# Pg10__NAND_SDMMC_Interface.net
KiCad netlist of a schematic drawn in Altium Designer
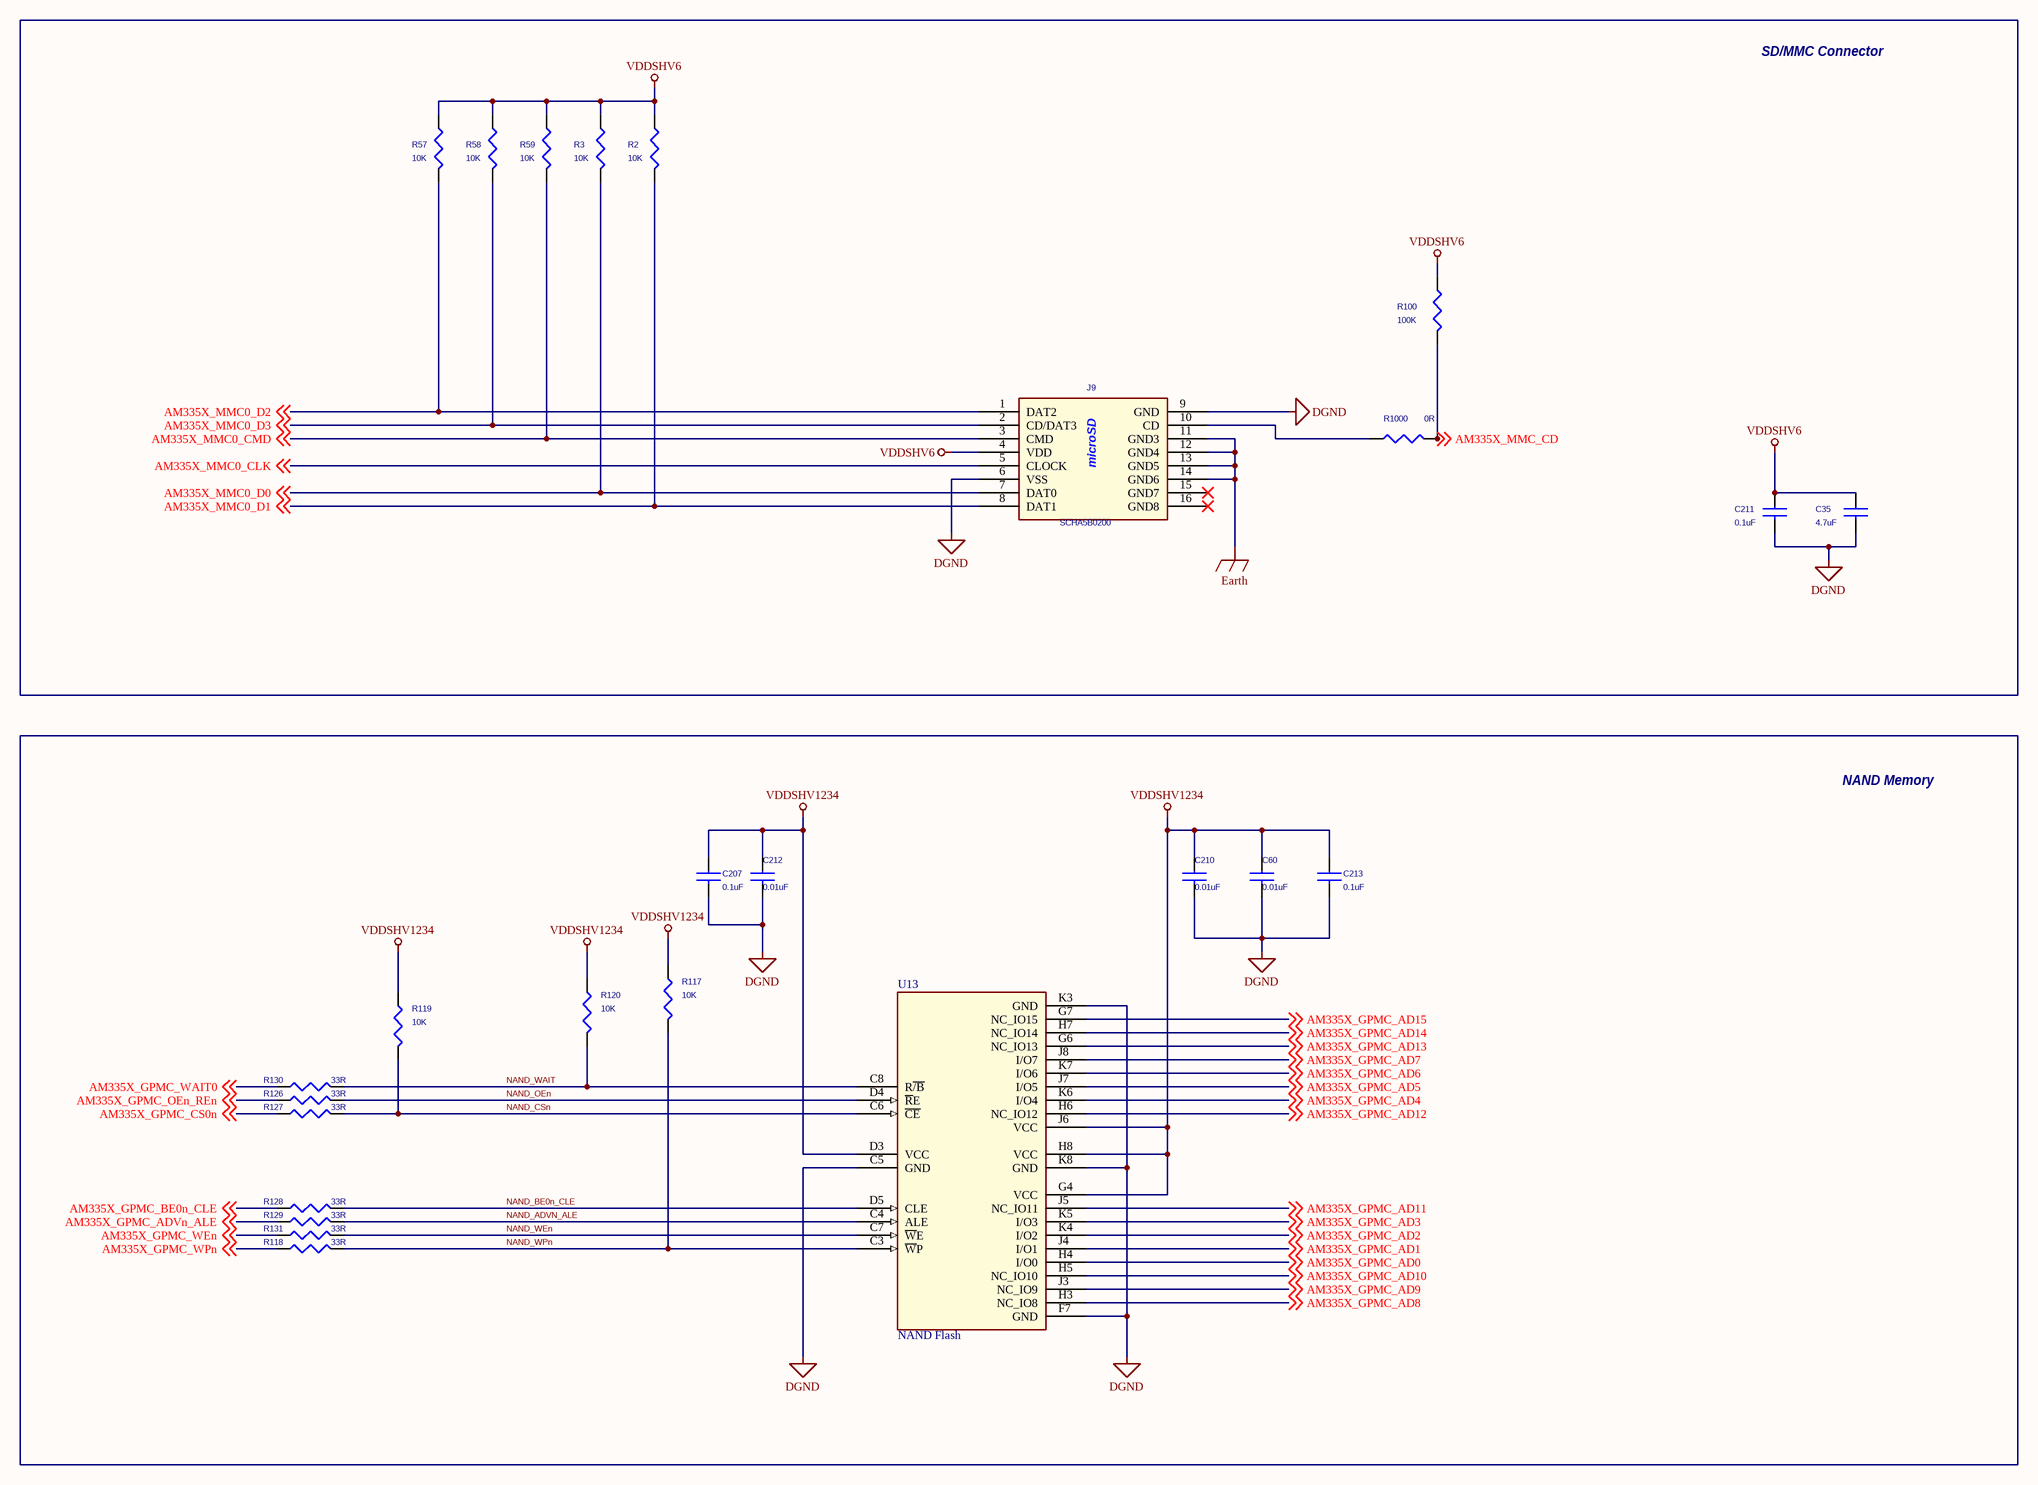
[diagram p0: Pg10_ NAND_SDMMC Interface.SchDoc]

(export (version "E")
  (design (tool "Eeschema 10.0.6"))
  (components
    (comp (ref "C35")
      (value "4.7uF")
      (footprint "SM-7351-CAP-0603")
      (fields (field (name "TIINTPARTNUMBER") "1C0103") (field (name "MFR") "Taiyo Yuden"))
      (libsource (lib "*") (part "4.7uFCapacitor16V10%0603"))
    )
    (comp (ref "C60")
      (value "0.01uF")
      (footprint "SM-7351-CAP-0402")
      (fields (field (name "TIINTPARTNUMBER") "1C0012") (field (name "MFR") "Panasonic"))
      (libsource (lib "*") (part "0.01uFCapacitor16V10%0402"))
    )
    (comp (ref "C207")
      (value "0.1uF")
      (footprint "SM-7351-CAP-0402")
      (fields (field (name "TIINTPARTNUMBER") "1C0089") (field (name "MFR") "Kemet"))
      (libsource (lib "*") (part "0.1uFCapacitor16V10%0402"))
    )
    (comp (ref "C210")
      (value "0.01uF")
      (footprint "SM-7351-CAP-0402")
      (fields (field (name "TIINTPARTNUMBER") "1C0012") (field (name "MFR") "Panasonic"))
      (libsource (lib "*") (part "0.01uFCapacitor16V10%0402"))
    )
    (comp (ref "C211")
      (value "0.1uF")
      (footprint "SM-7351-CAP-0402")
      (fields (field (name "TIINTPARTNUMBER") "1C0089") (field (name "MFR") "Kemet"))
      (libsource (lib "*") (part "0.1uFCapacitor16V10%0402_Dup1"))
    )
    (comp (ref "C212")
      (value "0.01uF")
      (footprint "SM-7351-CAP-0402")
      (fields (field (name "TIINTPARTNUMBER") "1C0012") (field (name "MFR") "Panasonic"))
      (libsource (lib "*") (part "0.01uFCapacitor16V10%0402"))
    )
    (comp (ref "C213")
      (value "0.1uF")
      (footprint "SM-7351-CAP-0402")
      (fields (field (name "TIINTPARTNUMBER") "1C0089") (field (name "MFR") "Kemet"))
      (libsource (lib "*") (part "0.1uFCapacitor16V10%0402"))
    )
    (comp (ref "J9")
      (value "SCHA5B0200")
      (footprint "micro SD")
      (fields (field (name "TIINTPARTNUMBER") "2C0102") (field (name "MFR") "ALPS"))
      (libsource (lib "*") (part "Conn_microSD_8"))
    )
    (comp (ref "R2")
      (value "10K")
      (footprint "SM-7351-RES-0402")
      (description "Resistor 10Kohm 1/16W 5% 0402")
      (fields (field (name "TIINTPARTNUMBER") "1R0168") (field (name "MFR") "Rohm"))
      (libsource (lib "*") (part "10KOhmResistor1/16W0402_Dup1"))
    )
    (comp (ref "R3")
      (value "10K")
      (footprint "SM-7351-RES-0402")
      (description "Resistor 10Kohm 1/16W 5% 0402")
      (fields (field (name "TIINTPARTNUMBER") "1R0168") (field (name "MFR") "Rohm"))
      (libsource (lib "*") (part "10KOhmResistor1/16W0402_Dup1"))
    )
    (comp (ref "R57")
      (value "10K")
      (footprint "SM-7351-RES-0402")
      (description "Resistor 10Kohm 1/16W 5% 0402")
      (fields (field (name "TIINTPARTNUMBER") "1R0168") (field (name "MFR") "Rohm"))
      (libsource (lib "*") (part "10KOhmResistor1/16W0402_Dup1"))
    )
    (comp (ref "R58")
      (value "10K")
      (footprint "SM-7351-RES-0402")
      (description "Resistor 10Kohm 1/16W 5% 0402")
      (fields (field (name "TIINTPARTNUMBER") "1R0168") (field (name "MFR") "Rohm"))
      (libsource (lib "*") (part "10KOhmResistor1/16W0402_Dup1"))
    )
    (comp (ref "R59")
      (value "10K")
      (footprint "SM-7351-RES-0402")
      (description "Resistor 10Kohm 1/16W 5% 0402")
      (fields (field (name "TIINTPARTNUMBER") "1R0168") (field (name "MFR") "Rohm"))
      (libsource (lib "*") (part "10KOhmResistor1/16W0402_Dup1"))
    )
    (comp (ref "R100")
      (value "100K")
      (footprint "SM-7351-RES-0402")
      (description "Resistor 470Kohm 1/16W 1% 0402")
      (fields (field (name "TIINTPARTNUMBER") "1R0190") (field (name "MFR") "Stackpole Electronics"))
      (libsource (lib "*") (part "470Kohm1/16W1%SMD0402"))
    )
    (comp (ref "R117")
      (value "10K")
      (footprint "SM-7351-RES-0402")
      (fields (field (name "TIINTPARTNUMBER") "1R0168") (field (name "MFR") "Rohm"))
      (libsource (lib "*") (part "10KOhmResistor1/16W0402"))
    )
    (comp (ref "R118")
      (value "33R")
      (footprint "SM-7351-RES-0402")
      (fields (field (name "TIINTPARTNUMBER") "1R0168") (field (name "MFR") "Rohm"))
      (libsource (lib "*") (part "10KOhmResistor1/16W0402"))
    )
    (comp (ref "R119")
      (value "10K")
      (footprint "SM-7351-RES-0402")
      (fields (field (name "TIINTPARTNUMBER") "1R0168") (field (name "MFR") "Rohm"))
      (libsource (lib "*") (part "10KOhmResistor1/16W0402"))
    )
    (comp (ref "R120")
      (value "10K")
      (footprint "SM-7351-RES-0402")
      (fields (field (name "TIINTPARTNUMBER") "1R0168") (field (name "MFR") "Rohm"))
      (libsource (lib "*") (part "10KOhmResistor1/16W0402"))
    )
    (comp (ref "R126")
      (value "33R")
      (footprint "SM-7351-RES-0402")
      (fields (field (name "TIINTPARTNUMBER") "1R0168") (field (name "MFR") "Rohm"))
      (libsource (lib "*") (part "10KOhmResistor1/16W0402"))
    )
    (comp (ref "R127")
      (value "33R")
      (footprint "SM-7351-RES-0402")
      (fields (field (name "TIINTPARTNUMBER") "1R0168") (field (name "MFR") "Rohm"))
      (libsource (lib "*") (part "10KOhmResistor1/16W0402"))
    )
    (comp (ref "R128")
      (value "33R")
      (footprint "SM-7351-RES-0402")
      (fields (field (name "TIINTPARTNUMBER") "1R0168") (field (name "MFR") "Rohm"))
      (libsource (lib "*") (part "10KOhmResistor1/16W0402"))
    )
    (comp (ref "R129")
      (value "33R")
      (footprint "SM-7351-RES-0402")
      (fields (field (name "TIINTPARTNUMBER") "1R0168") (field (name "MFR") "Rohm"))
      (libsource (lib "*") (part "10KOhmResistor1/16W0402"))
    )
    (comp (ref "R130")
      (value "33R")
      (footprint "SM-7351-RES-0402")
      (fields (field (name "TIINTPARTNUMBER") "1R0168") (field (name "MFR") "Rohm"))
      (libsource (lib "*") (part "10KOhmResistor1/16W0402"))
    )
    (comp (ref "R131")
      (value "33R")
      (footprint "SM-7351-RES-0402")
      (fields (field (name "TIINTPARTNUMBER") "1R0168") (field (name "MFR") "Rohm"))
      (libsource (lib "*") (part "10KOhmResistor1/16W0402"))
    )
    (comp (ref "R1000")
      (value "0R")
      (footprint "SM-7351-RES-0402")
      (description "Resistor 470Kohm 1/16W 1% 0402")
      (fields (field (name "TIINTPARTNUMBER") "1R0190") (field (name "MFR") "Stackpole Electronics"))
      (libsource (lib "*") (part "470Kohm1/16W1%SMD0402"))
    )
    (comp (ref "U13")
      (value "NAND Flash")
      (footprint "VFBGA - 63")
      (description "MT29F2Gxx")
      (fields (field (name "PARTNUMBER") "557-1486-2-ND"))
      (libsource (lib "ARMflash_mini") (part "NAND Flash"))
    )
  )
  (nets
    (net (code "1") (name "/NAND_ADVN_ALE") (class "Default")
      (node (ref "R129") (pin "1") (pinfunction "P1_1") (pintype "passive"))
      (node (ref "U13") (pin "C4") (pinfunction "ALE_C4") (pintype "input"))
    )
    (net (code "2") (name "/NAND_BE0n_CLE") (class "Default")
      (node (ref "R128") (pin "1") (pinfunction "P1_1") (pintype "passive"))
      (node (ref "U13") (pin "D5") (pinfunction "CLE_D5") (pintype "input"))
    )
    (net (code "3") (name "/NAND_CSn") (class "Default")
      (node (ref "R119") (pin "1") (pinfunction "P1_1") (pintype "passive"))
      (node (ref "R127") (pin "1") (pinfunction "P1_1") (pintype "passive"))
      (node (ref "U13") (pin "C6") (pinfunction "~{CE}_C6") (pintype "input"))
    )
    (net (code "4") (name "/NAND_OEn") (class "Default")
      (node (ref "R126") (pin "1") (pinfunction "P1_1") (pintype "passive"))
      (node (ref "U13") (pin "D4") (pinfunction "~{R}E_D4") (pintype "input"))
    )
    (net (code "5") (name "/NAND_WAIT") (class "Default")
      (node (ref "R120") (pin "1") (pinfunction "P1_1") (pintype "passive"))
      (node (ref "R130") (pin "1") (pinfunction "P1_1") (pintype "passive"))
      (node (ref "U13") (pin "C8") (pinfunction "R~{/B}_C8") (pintype "open_collector"))
    )
    (net (code "6") (name "/NAND_WEn") (class "Default")
      (node (ref "R131") (pin "1") (pinfunction "P1_1") (pintype "passive"))
      (node (ref "U13") (pin "C7") (pinfunction "~{W}E_C7") (pintype "input"))
    )
    (net (code "7") (name "/NAND_WPn") (class "Default")
      (node (ref "R117") (pin "1") (pinfunction "P1_1") (pintype "passive"))
      (node (ref "R118") (pin "1") (pinfunction "P1_1") (pintype "passive"))
      (node (ref "U13") (pin "C3") (pinfunction "~{W}P_C3") (pintype "input"))
    )
    (net (code "8") (name "AM335X_GPMC_AD0") (class "Default")
      (node (ref "U13") (pin "H4") (pinfunction "I/O0_H4") (pintype "tri_state"))
    )
    (net (code "9") (name "AM335X_GPMC_AD1") (class "Default")
      (node (ref "U13") (pin "J4") (pinfunction "I/O1_J4") (pintype "tri_state"))
    )
    (net (code "10") (name "AM335X_GPMC_AD2") (class "Default")
      (node (ref "U13") (pin "K4") (pinfunction "I/O2_K4") (pintype "tri_state"))
    )
    (net (code "11") (name "AM335X_GPMC_AD3") (class "Default")
      (node (ref "U13") (pin "K5") (pinfunction "I/O3_K5") (pintype "tri_state"))
    )
    (net (code "12") (name "AM335X_GPMC_AD4") (class "Default")
      (node (ref "U13") (pin "K6") (pinfunction "I/O4_K6") (pintype "tri_state"))
    )
    (net (code "13") (name "AM335X_GPMC_AD5") (class "Default")
      (node (ref "U13") (pin "J7") (pinfunction "I/O5_J7") (pintype "tri_state"))
    )
    (net (code "14") (name "AM335X_GPMC_AD6") (class "Default")
      (node (ref "U13") (pin "K7") (pinfunction "I/O6_K7") (pintype "tri_state"))
    )
    (net (code "15") (name "AM335X_GPMC_AD7") (class "Default")
      (node (ref "U13") (pin "J8") (pinfunction "I/O7_J8") (pintype "tri_state"))
    )
    (net (code "16") (name "AM335X_GPMC_AD8") (class "Default")
      (node (ref "U13") (pin "H3") (pinfunction "NC_IO8_H3") (pintype "passive"))
    )
    (net (code "17") (name "AM335X_GPMC_AD9") (class "Default")
      (node (ref "U13") (pin "J3") (pinfunction "NC_IO9_J3") (pintype "passive"))
    )
    (net (code "18") (name "AM335X_GPMC_AD10") (class "Default")
      (node (ref "U13") (pin "H5") (pinfunction "NC_IO10_H5") (pintype "passive"))
    )
    (net (code "19") (name "AM335X_GPMC_AD11") (class "Default")
      (node (ref "U13") (pin "J5") (pinfunction "NC_IO11_J5") (pintype "passive"))
    )
    (net (code "20") (name "AM335X_GPMC_AD12") (class "Default")
      (node (ref "U13") (pin "H6") (pinfunction "NC_IO12_H6") (pintype "passive"))
    )
    (net (code "21") (name "AM335X_GPMC_AD13") (class "Default")
      (node (ref "U13") (pin "G6") (pinfunction "NC_IO13_G6") (pintype "passive"))
    )
    (net (code "22") (name "AM335X_GPMC_AD14") (class "Default")
      (node (ref "U13") (pin "H7") (pinfunction "NC_IO14_H7") (pintype "passive"))
    )
    (net (code "23") (name "AM335X_GPMC_AD15") (class "Default")
      (node (ref "U13") (pin "G7") (pinfunction "NC_IO15_G7") (pintype "passive"))
    )
    (net (code "24") (name "AM335X_GPMC_ADVn_ALE") (class "Default")
      (node (ref "R129") (pin "2") (pinfunction "P2_2") (pintype "passive"))
    )
    (net (code "25") (name "AM335X_GPMC_BE0n_CLE") (class "Default")
      (node (ref "R128") (pin "2") (pinfunction "P2_2") (pintype "passive"))
    )
    (net (code "26") (name "AM335X_GPMC_CS0n") (class "Default")
      (node (ref "R127") (pin "2") (pinfunction "P2_2") (pintype "passive"))
    )
    (net (code "27") (name "AM335X_GPMC_OEn_REn") (class "Default")
      (node (ref "R126") (pin "2") (pinfunction "P2_2") (pintype "passive"))
    )
    (net (code "28") (name "AM335X_GPMC_WAIT0") (class "Default")
      (node (ref "R130") (pin "2") (pinfunction "P2_2") (pintype "passive"))
    )
    (net (code "29") (name "AM335X_GPMC_WEn") (class "Default")
      (node (ref "R131") (pin "2") (pinfunction "P2_2") (pintype "passive"))
    )
    (net (code "30") (name "AM335X_GPMC_WPn") (class "Default")
      (node (ref "R118") (pin "2") (pinfunction "P2_2") (pintype "passive"))
    )
    (net (code "31") (name "AM335X_MMC0_CLK") (class "Default")
      (node (ref "J9") (pin "5") (pinfunction "CLOCK_5") (pintype "passive"))
    )
    (net (code "32") (name "AM335X_MMC0_CMD") (class "Default")
      (node (ref "J9") (pin "3") (pinfunction "CMD_3") (pintype "passive"))
      (node (ref "R59") (pin "1") (pinfunction "P1_1") (pintype "passive"))
    )
    (net (code "33") (name "AM335X_MMC0_D0") (class "Default")
      (node (ref "J9") (pin "7") (pinfunction "DAT0_7") (pintype "passive"))
      (node (ref "R3") (pin "1") (pinfunction "P1_1") (pintype "passive"))
    )
    (net (code "34") (name "AM335X_MMC0_D1") (class "Default")
      (node (ref "J9") (pin "8") (pinfunction "DAT1_8") (pintype "passive"))
      (node (ref "R2") (pin "1") (pinfunction "P1_1") (pintype "passive"))
    )
    (net (code "35") (name "AM335X_MMC0_D2") (class "Default")
      (node (ref "J9") (pin "1") (pinfunction "DAT2_1") (pintype "passive"))
      (node (ref "R57") (pin "1") (pinfunction "P1_1") (pintype "passive"))
    )
    (net (code "36") (name "AM335X_MMC0_D3") (class "Default")
      (node (ref "J9") (pin "2") (pinfunction "CD/DAT3_2") (pintype "passive"))
      (node (ref "R58") (pin "1") (pinfunction "P1_1") (pintype "passive"))
    )
    (net (code "37") (name "AM335X_MMC_CD") (class "Default")
      (node (ref "R100") (pin "1") (pinfunction "P1_1") (pintype "passive"))
      (node (ref "R1000") (pin "1") (pinfunction "P1_1") (pintype "passive"))
    )
    (net (code "38") (name "DGND") (class "Default")
      (node (ref "C207") (pin "2") (pinfunction "2_2") (pintype "passive"))
      (node (ref "C210") (pin "2") (pinfunction "2_2") (pintype "passive"))
      (node (ref "C211") (pin "2") (pinfunction "2_2") (pintype "passive"))
      (node (ref "C212") (pin "2") (pinfunction "2_2") (pintype "passive"))
      (node (ref "C213") (pin "2") (pinfunction "2_2") (pintype "passive"))
      (node (ref "C35") (pin "2") (pinfunction "2_2") (pintype "passive"))
      (node (ref "C60") (pin "2") (pinfunction "2_2") (pintype "passive"))
      (node (ref "J9") (pin "6") (pinfunction "VSS_6") (pintype "power_in"))
      (node (ref "J9") (pin "9") (pinfunction "GND_9") (pintype "power_in"))
      (node (ref "U13") (pin "C5") (pinfunction "GND_C5") (pintype "power_in"))
      (node (ref "U13") (pin "F7") (pinfunction "GND_F7") (pintype "power_in"))
      (node (ref "U13") (pin "K3") (pinfunction "GND_K3") (pintype "power_in"))
      (node (ref "U13") (pin "K8") (pinfunction "GND_K8") (pintype "power_in"))
    )
    (net (code "39") (name "Earth") (class "Default")
      (node (ref "J9") (pin "11") (pinfunction "GND3_11") (pintype "power_in"))
      (node (ref "J9") (pin "12") (pinfunction "GND4_12") (pintype "power_in"))
      (node (ref "J9") (pin "13") (pinfunction "GND5_13") (pintype "power_in"))
      (node (ref "J9") (pin "14") (pinfunction "GND6_14") (pintype "power_in"))
    )
    (net (code "40") (name "Net-(J9-CD)") (class "Default")
      (node (ref "J9") (pin "10") (pinfunction "CD_10") (pintype "passive"))
      (node (ref "R1000") (pin "2") (pinfunction "P2_2") (pintype "passive"))
    )
    (net (code "41") (name "VDDSHV6") (class "Default")
      (node (ref "C211") (pin "1") (pinfunction "1_1") (pintype "passive"))
      (node (ref "C35") (pin "1") (pinfunction "1_1") (pintype "passive"))
      (node (ref "J9") (pin "4") (pinfunction "VDD_4") (pintype "power_in"))
      (node (ref "R100") (pin "2") (pinfunction "P2_2") (pintype "passive"))
      (node (ref "R2") (pin "2") (pinfunction "P2_2") (pintype "passive"))
      (node (ref "R3") (pin "2") (pinfunction "P2_2") (pintype "passive"))
      (node (ref "R57") (pin "2") (pinfunction "P2_2") (pintype "passive"))
      (node (ref "R58") (pin "2") (pinfunction "P2_2") (pintype "passive"))
      (node (ref "R59") (pin "2") (pinfunction "P2_2") (pintype "passive"))
    )
    (net (code "42") (name "VDDSHV1234") (class "Default")
      (node (ref "C207") (pin "1") (pinfunction "1_1") (pintype "passive"))
      (node (ref "C210") (pin "1") (pinfunction "1_1") (pintype "passive"))
      (node (ref "C212") (pin "1") (pinfunction "1_1") (pintype "passive"))
      (node (ref "C213") (pin "1") (pinfunction "1_1") (pintype "passive"))
      (node (ref "C60") (pin "1") (pinfunction "1_1") (pintype "passive"))
      (node (ref "R117") (pin "2") (pinfunction "P2_2") (pintype "passive"))
      (node (ref "R119") (pin "2") (pinfunction "P2_2") (pintype "passive"))
      (node (ref "R120") (pin "2") (pinfunction "P2_2") (pintype "passive"))
      (node (ref "U13") (pin "D3") (pinfunction "VCC_D3") (pintype "power_in"))
      (node (ref "U13") (pin "G4") (pinfunction "VCC_G4") (pintype "power_in"))
      (node (ref "U13") (pin "H8") (pinfunction "VCC_H8") (pintype "power_in"))
      (node (ref "U13") (pin "J6") (pinfunction "VCC_J6") (pintype "power_in"))
    )
    (net (code "43") (name "unconnected-(J9-GND7-Pad15)") (class "Default")
      (node (ref "J9") (pin "15") (pinfunction "GND7_15") (pintype "power_in+no_connect"))
    )
    (net (code "44") (name "unconnected-(J9-GND8-Pad16)") (class "Default")
      (node (ref "J9") (pin "16") (pinfunction "GND8_16") (pintype "power_in+no_connect"))
    )
  )
)
